# ArmMount_Board_2.net
KiCad netlist of a schematic drawn in EAGLE
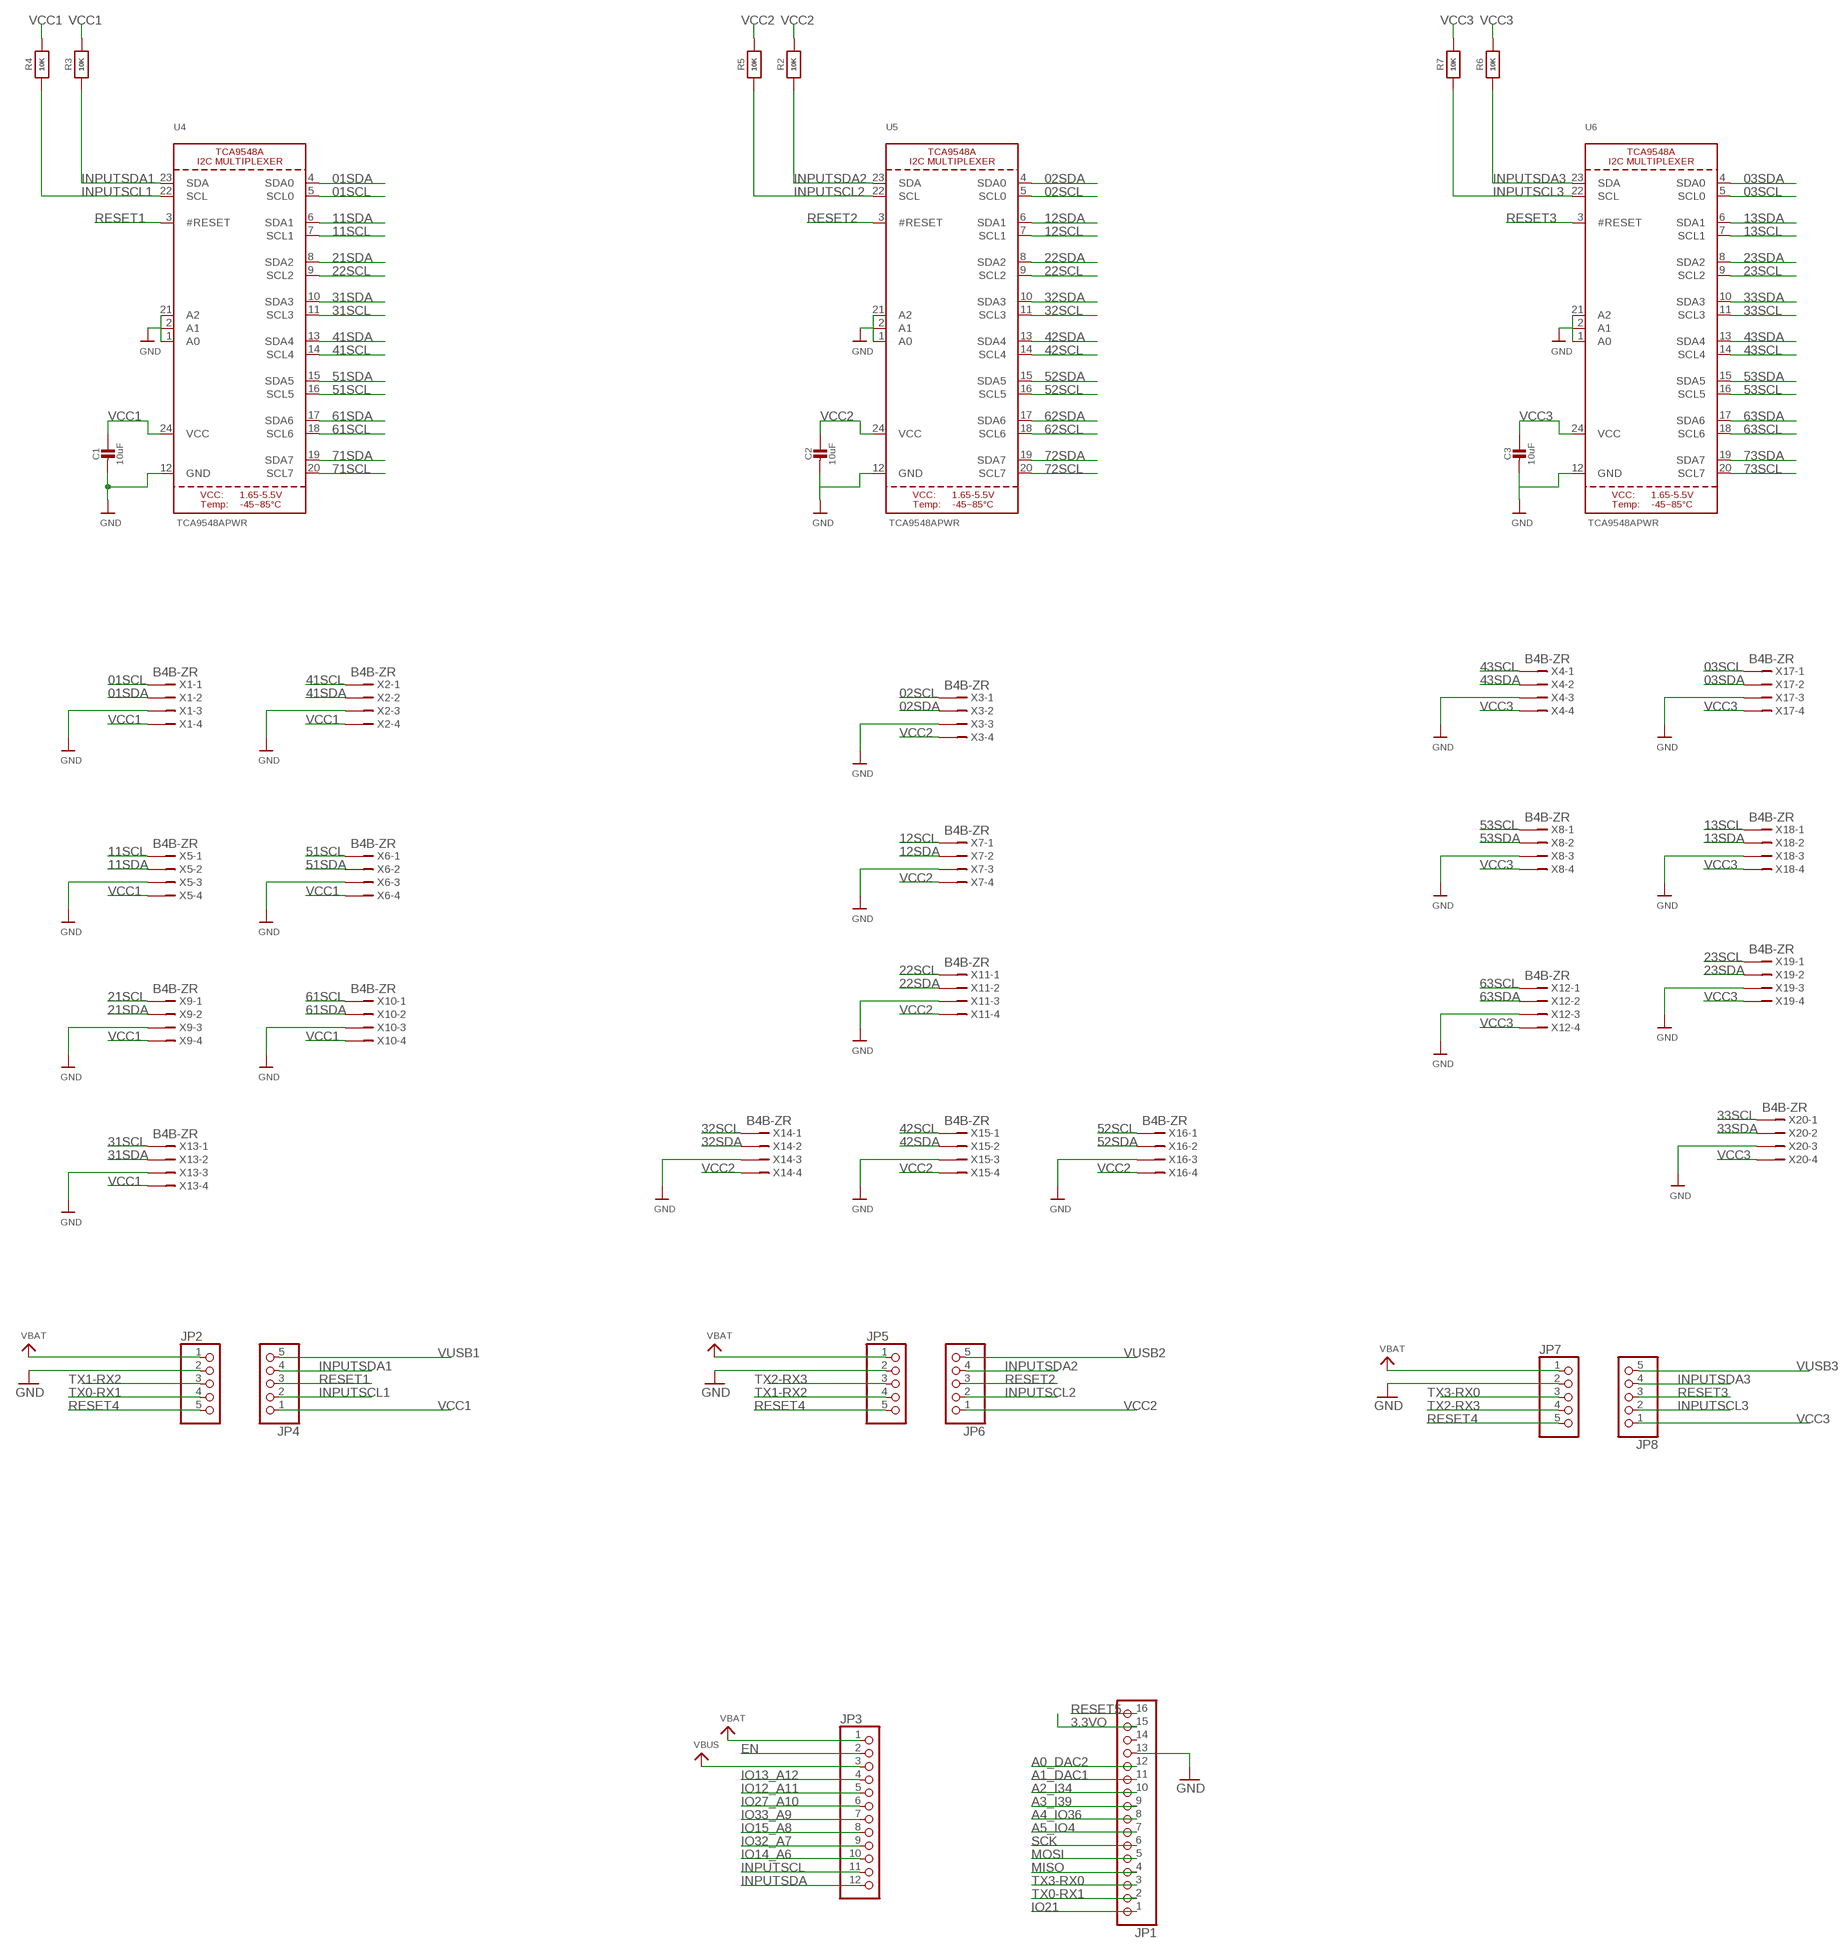
[diagram p0: schematic, sheet 1]

(export (version "E")
  (design (tool "Eeschema 10.0.6"))
  (components
    (comp (ref "C1")
      (value "10uF")
      (footprint "eagle-import:0805-NO")
      (libsource (lib "eagle-import") (part "CAP_CERAMIC0805-NOOUTLINE"))
    )
    (comp (ref "C2")
      (value "10uF")
      (footprint "eagle-import:0805-NO")
      (libsource (lib "eagle-import") (part "CAP_CERAMIC0805-NOOUTLINE"))
    )
    (comp (ref "C3")
      (value "10uF")
      (footprint "eagle-import:0805-NO")
      (libsource (lib "eagle-import") (part "CAP_CERAMIC0805-NOOUTLINE"))
    )
    (comp (ref "JP1")
      (value "HEADER-1X16_MIN")
      (footprint "eagle-import:1X16_ROUND_MIN")
      (libsource (lib "eagle-import") (part "HEADER-1X16_MIN"))
    )
    (comp (ref "JP2")
      (value "HEADER-1X576MIL")
      (footprint "eagle-import:1X05_ROUND_76")
      (libsource (lib "eagle-import") (part "HEADER-1X576MIL"))
    )
    (comp (ref "JP3")
      (value "HEADER-1X12_MIN")
      (footprint "eagle-import:1X12_ROUND_MIN")
      (libsource (lib "eagle-import") (part "HEADER-1X12_MIN"))
    )
    (comp (ref "JP4")
      (value "HEADER-1X576MIL")
      (footprint "eagle-import:1X05_ROUND_76")
      (libsource (lib "eagle-import") (part "HEADER-1X576MIL"))
    )
    (comp (ref "JP5")
      (value "HEADER-1X576MIL")
      (footprint "eagle-import:1X05_ROUND_76")
      (libsource (lib "eagle-import") (part "HEADER-1X576MIL"))
    )
    (comp (ref "JP6")
      (value "HEADER-1X576MIL")
      (footprint "eagle-import:1X05_ROUND_76")
      (libsource (lib "eagle-import") (part "HEADER-1X576MIL"))
    )
    (comp (ref "JP7")
      (value "HEADER-1X576MIL")
      (footprint "eagle-import:1X05_ROUND_76")
      (libsource (lib "eagle-import") (part "HEADER-1X576MIL"))
    )
    (comp (ref "JP8")
      (value "HEADER-1X576MIL")
      (footprint "eagle-import:1X05_ROUND_76")
      (libsource (lib "eagle-import") (part "HEADER-1X576MIL"))
    )
    (comp (ref "R2")
      (value "10K")
      (footprint "eagle-import:0805-NO")
      (libsource (lib "eagle-import") (part "RESISTOR0805_NOOUTLINE"))
    )
    (comp (ref "R3")
      (value "10K")
      (footprint "eagle-import:0805-NO")
      (libsource (lib "eagle-import") (part "RESISTOR0805_NOOUTLINE"))
    )
    (comp (ref "R4")
      (value "10K")
      (footprint "eagle-import:0805-NO")
      (libsource (lib "eagle-import") (part "RESISTOR0805_NOOUTLINE"))
    )
    (comp (ref "R5")
      (value "10K")
      (footprint "eagle-import:0805-NO")
      (libsource (lib "eagle-import") (part "RESISTOR0805_NOOUTLINE"))
    )
    (comp (ref "R6")
      (value "10K")
      (footprint "eagle-import:0805-NO")
      (libsource (lib "eagle-import") (part "RESISTOR0805_NOOUTLINE"))
    )
    (comp (ref "R7")
      (value "10K")
      (footprint "eagle-import:0805-NO")
      (libsource (lib "eagle-import") (part "RESISTOR0805_NOOUTLINE"))
    )
    (comp (ref "U4")
      (value "TCA9548APWR")
      (footprint "eagle-import:TSSOP24")
      (libsource (lib "eagle-import") (part "TCA9548A"))
    )
    (comp (ref "U5")
      (value "TCA9548APWR")
      (footprint "eagle-import:TSSOP24")
      (libsource (lib "eagle-import") (part "TCA9548A"))
    )
    (comp (ref "U6")
      (value "TCA9548APWR")
      (footprint "eagle-import:TSSOP24")
      (libsource (lib "eagle-import") (part "TCA9548A"))
    )
    (comp (ref "X1")
      (value "B4B-ZR")
      (footprint "eagle-import:B4B-ZR")
      (fields (field (name "MF") "FARNELL") (field (name "MPN") "B4B-ZR(LF)(SN)"))
      (libsource (lib "eagle-import") (part "?4B-ZRB"))
    )
    (comp (ref "X2")
      (value "B4B-ZR")
      (footprint "eagle-import:B4B-ZR")
      (fields (field (name "MF") "FARNELL") (field (name "MPN") "B4B-ZR(LF)(SN)"))
      (libsource (lib "eagle-import") (part "?4B-ZRB"))
    )
    (comp (ref "X3")
      (value "B4B-ZR")
      (footprint "eagle-import:B4B-ZR")
      (fields (field (name "MF") "FARNELL") (field (name "MPN") "B4B-ZR(LF)(SN)"))
      (libsource (lib "eagle-import") (part "?4B-ZRB"))
    )
    (comp (ref "X4")
      (value "B4B-ZR")
      (footprint "eagle-import:B4B-ZR")
      (fields (field (name "MF") "FARNELL") (field (name "MPN") "B4B-ZR(LF)(SN)"))
      (libsource (lib "eagle-import") (part "?4B-ZRB"))
    )
    (comp (ref "X5")
      (value "B4B-ZR")
      (footprint "eagle-import:B4B-ZR")
      (fields (field (name "MF") "FARNELL") (field (name "MPN") "B4B-ZR(LF)(SN)"))
      (libsource (lib "eagle-import") (part "?4B-ZRB"))
    )
    (comp (ref "X6")
      (value "B4B-ZR")
      (footprint "eagle-import:B4B-ZR")
      (fields (field (name "MF") "FARNELL") (field (name "MPN") "B4B-ZR(LF)(SN)"))
      (libsource (lib "eagle-import") (part "?4B-ZRB"))
    )
    (comp (ref "X7")
      (value "B4B-ZR")
      (footprint "eagle-import:B4B-ZR")
      (fields (field (name "MF") "FARNELL") (field (name "MPN") "B4B-ZR(LF)(SN)"))
      (libsource (lib "eagle-import") (part "?4B-ZRB"))
    )
    (comp (ref "X8")
      (value "B4B-ZR")
      (footprint "eagle-import:B4B-ZR")
      (fields (field (name "MF") "FARNELL") (field (name "MPN") "B4B-ZR(LF)(SN)"))
      (libsource (lib "eagle-import") (part "?4B-ZRB"))
    )
    (comp (ref "X9")
      (value "B4B-ZR")
      (footprint "eagle-import:B4B-ZR")
      (fields (field (name "MF") "FARNELL") (field (name "MPN") "B4B-ZR(LF)(SN)"))
      (libsource (lib "eagle-import") (part "?4B-ZRB"))
    )
    (comp (ref "X10")
      (value "B4B-ZR")
      (footprint "eagle-import:B4B-ZR")
      (fields (field (name "MF") "FARNELL") (field (name "MPN") "B4B-ZR(LF)(SN)"))
      (libsource (lib "eagle-import") (part "?4B-ZRB"))
    )
    (comp (ref "X11")
      (value "B4B-ZR")
      (footprint "eagle-import:B4B-ZR")
      (fields (field (name "MF") "FARNELL") (field (name "MPN") "B4B-ZR(LF)(SN)"))
      (libsource (lib "eagle-import") (part "?4B-ZRB"))
    )
    (comp (ref "X12")
      (value "B4B-ZR")
      (footprint "eagle-import:B4B-ZR")
      (fields (field (name "MF") "FARNELL") (field (name "MPN") "B4B-ZR(LF)(SN)"))
      (libsource (lib "eagle-import") (part "?4B-ZRB"))
    )
    (comp (ref "X13")
      (value "B4B-ZR")
      (footprint "eagle-import:B4B-ZR")
      (fields (field (name "MF") "FARNELL") (field (name "MPN") "B4B-ZR(LF)(SN)"))
      (libsource (lib "eagle-import") (part "?4B-ZRB"))
    )
    (comp (ref "X14")
      (value "B4B-ZR")
      (footprint "eagle-import:B4B-ZR")
      (fields (field (name "MF") "FARNELL") (field (name "MPN") "B4B-ZR(LF)(SN)"))
      (libsource (lib "eagle-import") (part "?4B-ZRB"))
    )
    (comp (ref "X15")
      (value "B4B-ZR")
      (footprint "eagle-import:B4B-ZR")
      (fields (field (name "MF") "FARNELL") (field (name "MPN") "B4B-ZR(LF)(SN)"))
      (libsource (lib "eagle-import") (part "?4B-ZRB"))
    )
    (comp (ref "X16")
      (value "B4B-ZR")
      (footprint "eagle-import:B4B-ZR")
      (fields (field (name "MF") "FARNELL") (field (name "MPN") "B4B-ZR(LF)(SN)"))
      (libsource (lib "eagle-import") (part "?4B-ZRB"))
    )
    (comp (ref "X17")
      (value "B4B-ZR")
      (footprint "eagle-import:B4B-ZR")
      (fields (field (name "MF") "FARNELL") (field (name "MPN") "B4B-ZR(LF)(SN)"))
      (libsource (lib "eagle-import") (part "?4B-ZRB"))
    )
    (comp (ref "X18")
      (value "B4B-ZR")
      (footprint "eagle-import:B4B-ZR")
      (fields (field (name "MF") "FARNELL") (field (name "MPN") "B4B-ZR(LF)(SN)"))
      (libsource (lib "eagle-import") (part "?4B-ZRB"))
    )
    (comp (ref "X19")
      (value "B4B-ZR")
      (footprint "eagle-import:B4B-ZR")
      (fields (field (name "MF") "FARNELL") (field (name "MPN") "B4B-ZR(LF)(SN)"))
      (libsource (lib "eagle-import") (part "?4B-ZRB"))
    )
    (comp (ref "X20")
      (value "B4B-ZR")
      (footprint "eagle-import:B4B-ZR")
      (fields (field (name "MF") "FARNELL") (field (name "MPN") "B4B-ZR(LF)(SN)"))
      (libsource (lib "eagle-import") (part "?4B-ZRB"))
    )
  )
  (nets
    (net (code "1") (name "/01SCL") (class "Default")
      (node (ref "U4") (pin "5") (pinfunction "SCL0_5") (pintype "bidirectional"))
      (node (ref "X1") (pin "1") (pinfunction "1_1") (pintype "passive"))
    )
    (net (code "2") (name "/01SDA") (class "Default")
      (node (ref "U4") (pin "4") (pinfunction "SDA0_4") (pintype "bidirectional"))
      (node (ref "X1") (pin "2") (pinfunction "1_2") (pintype "passive"))
    )
    (net (code "3") (name "/02SCL") (class "Default")
      (node (ref "U5") (pin "5") (pinfunction "SCL0_5") (pintype "bidirectional"))
      (node (ref "X3") (pin "1") (pinfunction "1_1") (pintype "passive"))
    )
    (net (code "4") (name "/02SDA") (class "Default")
      (node (ref "U5") (pin "4") (pinfunction "SDA0_4") (pintype "bidirectional"))
      (node (ref "X3") (pin "2") (pinfunction "1_2") (pintype "passive"))
    )
    (net (code "5") (name "/3.3VO") (class "Default")
      (node (ref "JP1") (pin "15") (pinfunction "15_15") (pintype "passive"))
    )
    (net (code "6") (name "/03SCL") (class "Default")
      (node (ref "U6") (pin "5") (pinfunction "SCL0_5") (pintype "bidirectional"))
      (node (ref "X17") (pin "1") (pinfunction "1_1") (pintype "passive"))
    )
    (net (code "7") (name "/03SDA") (class "Default")
      (node (ref "U6") (pin "4") (pinfunction "SDA0_4") (pintype "bidirectional"))
      (node (ref "X17") (pin "2") (pinfunction "1_2") (pintype "passive"))
    )
    (net (code "8") (name "/11SCL") (class "Default")
      (node (ref "U4") (pin "7") (pinfunction "SCL1_7") (pintype "bidirectional"))
      (node (ref "X5") (pin "1") (pinfunction "1_1") (pintype "passive"))
    )
    (net (code "9") (name "/11SDA") (class "Default")
      (node (ref "U4") (pin "6") (pinfunction "SDA1_6") (pintype "bidirectional"))
      (node (ref "X5") (pin "2") (pinfunction "1_2") (pintype "passive"))
    )
    (net (code "10") (name "/12SCL") (class "Default")
      (node (ref "U5") (pin "7") (pinfunction "SCL1_7") (pintype "bidirectional"))
      (node (ref "X7") (pin "1") (pinfunction "1_1") (pintype "passive"))
    )
    (net (code "11") (name "/12SDA") (class "Default")
      (node (ref "U5") (pin "6") (pinfunction "SDA1_6") (pintype "bidirectional"))
      (node (ref "X7") (pin "2") (pinfunction "1_2") (pintype "passive"))
    )
    (net (code "12") (name "/13SCL") (class "Default")
      (node (ref "U6") (pin "7") (pinfunction "SCL1_7") (pintype "bidirectional"))
      (node (ref "X18") (pin "1") (pinfunction "1_1") (pintype "passive"))
    )
    (net (code "13") (name "/13SDA") (class "Default")
      (node (ref "U6") (pin "6") (pinfunction "SDA1_6") (pintype "bidirectional"))
      (node (ref "X18") (pin "2") (pinfunction "1_2") (pintype "passive"))
    )
    (net (code "14") (name "/21SCL") (class "Default")
      (node (ref "X9") (pin "1") (pinfunction "1_1") (pintype "passive"))
    )
    (net (code "15") (name "/21SDA") (class "Default")
      (node (ref "U4") (pin "8") (pinfunction "SDA2_8") (pintype "bidirectional"))
      (node (ref "X9") (pin "2") (pinfunction "1_2") (pintype "passive"))
    )
    (net (code "16") (name "/22SCL") (class "Default")
      (node (ref "U4") (pin "9") (pinfunction "SCL2_9") (pintype "bidirectional"))
      (node (ref "U5") (pin "9") (pinfunction "SCL2_9") (pintype "bidirectional"))
      (node (ref "X11") (pin "1") (pinfunction "1_1") (pintype "passive"))
    )
    (net (code "17") (name "/22SDA") (class "Default")
      (node (ref "U5") (pin "8") (pinfunction "SDA2_8") (pintype "bidirectional"))
      (node (ref "X11") (pin "2") (pinfunction "1_2") (pintype "passive"))
    )
    (net (code "18") (name "/23SCL") (class "Default")
      (node (ref "U6") (pin "9") (pinfunction "SCL2_9") (pintype "bidirectional"))
      (node (ref "X19") (pin "1") (pinfunction "1_1") (pintype "passive"))
    )
    (net (code "19") (name "/23SDA") (class "Default")
      (node (ref "U6") (pin "8") (pinfunction "SDA2_8") (pintype "bidirectional"))
      (node (ref "X19") (pin "2") (pinfunction "1_2") (pintype "passive"))
    )
    (net (code "20") (name "/31SCL") (class "Default")
      (node (ref "U4") (pin "11") (pinfunction "SCL3_11") (pintype "bidirectional"))
      (node (ref "X13") (pin "1") (pinfunction "1_1") (pintype "passive"))
    )
    (net (code "21") (name "/31SDA") (class "Default")
      (node (ref "U4") (pin "10") (pinfunction "SDA3_10") (pintype "bidirectional"))
      (node (ref "X13") (pin "2") (pinfunction "1_2") (pintype "passive"))
    )
    (net (code "22") (name "/32SCL") (class "Default")
      (node (ref "U5") (pin "11") (pinfunction "SCL3_11") (pintype "bidirectional"))
      (node (ref "X14") (pin "1") (pinfunction "1_1") (pintype "passive"))
    )
    (net (code "23") (name "/32SDA") (class "Default")
      (node (ref "U5") (pin "10") (pinfunction "SDA3_10") (pintype "bidirectional"))
      (node (ref "X14") (pin "2") (pinfunction "1_2") (pintype "passive"))
    )
    (net (code "24") (name "/33SCL") (class "Default")
      (node (ref "U6") (pin "11") (pinfunction "SCL3_11") (pintype "bidirectional"))
      (node (ref "X20") (pin "1") (pinfunction "1_1") (pintype "passive"))
    )
    (net (code "25") (name "/33SDA") (class "Default")
      (node (ref "U6") (pin "10") (pinfunction "SDA3_10") (pintype "bidirectional"))
      (node (ref "X20") (pin "2") (pinfunction "1_2") (pintype "passive"))
    )
    (net (code "26") (name "/41SCL") (class "Default")
      (node (ref "U4") (pin "14") (pinfunction "SCL4_14") (pintype "bidirectional"))
      (node (ref "X2") (pin "1") (pinfunction "1_1") (pintype "passive"))
    )
    (net (code "27") (name "/41SDA") (class "Default")
      (node (ref "U4") (pin "13") (pinfunction "SDA4_13") (pintype "bidirectional"))
      (node (ref "X2") (pin "2") (pinfunction "1_2") (pintype "passive"))
    )
    (net (code "28") (name "/42SCL") (class "Default")
      (node (ref "U5") (pin "14") (pinfunction "SCL4_14") (pintype "bidirectional"))
      (node (ref "X15") (pin "1") (pinfunction "1_1") (pintype "passive"))
    )
    (net (code "29") (name "/42SDA") (class "Default")
      (node (ref "U5") (pin "13") (pinfunction "SDA4_13") (pintype "bidirectional"))
      (node (ref "X15") (pin "2") (pinfunction "1_2") (pintype "passive"))
    )
    (net (code "30") (name "/43SCL") (class "Default")
      (node (ref "U6") (pin "14") (pinfunction "SCL4_14") (pintype "bidirectional"))
      (node (ref "X4") (pin "1") (pinfunction "1_1") (pintype "passive"))
    )
    (net (code "31") (name "/43SDA") (class "Default")
      (node (ref "U6") (pin "13") (pinfunction "SDA4_13") (pintype "bidirectional"))
      (node (ref "X4") (pin "2") (pinfunction "1_2") (pintype "passive"))
    )
    (net (code "32") (name "/51SCL") (class "Default")
      (node (ref "U4") (pin "16") (pinfunction "SCL5_16") (pintype "bidirectional"))
      (node (ref "X6") (pin "1") (pinfunction "1_1") (pintype "passive"))
    )
    (net (code "33") (name "/51SDA") (class "Default")
      (node (ref "U4") (pin "15") (pinfunction "SDA5_15") (pintype "bidirectional"))
      (node (ref "X6") (pin "2") (pinfunction "1_2") (pintype "passive"))
    )
    (net (code "34") (name "/52SCL") (class "Default")
      (node (ref "U5") (pin "16") (pinfunction "SCL5_16") (pintype "bidirectional"))
      (node (ref "X16") (pin "1") (pinfunction "1_1") (pintype "passive"))
    )
    (net (code "35") (name "/52SDA") (class "Default")
      (node (ref "U5") (pin "15") (pinfunction "SDA5_15") (pintype "bidirectional"))
      (node (ref "X16") (pin "2") (pinfunction "1_2") (pintype "passive"))
    )
    (net (code "36") (name "/53SCL") (class "Default")
      (node (ref "U6") (pin "16") (pinfunction "SCL5_16") (pintype "bidirectional"))
      (node (ref "X8") (pin "1") (pinfunction "1_1") (pintype "passive"))
    )
    (net (code "37") (name "/53SDA") (class "Default")
      (node (ref "U6") (pin "15") (pinfunction "SDA5_15") (pintype "bidirectional"))
      (node (ref "X8") (pin "2") (pinfunction "1_2") (pintype "passive"))
    )
    (net (code "38") (name "/61SCL") (class "Default")
      (node (ref "U4") (pin "18") (pinfunction "SCL6_18") (pintype "bidirectional"))
      (node (ref "X10") (pin "1") (pinfunction "1_1") (pintype "passive"))
    )
    (net (code "39") (name "/61SDA") (class "Default")
      (node (ref "U4") (pin "17") (pinfunction "SDA6_17") (pintype "bidirectional"))
      (node (ref "X10") (pin "2") (pinfunction "1_2") (pintype "passive"))
    )
    (net (code "40") (name "/62SCL") (class "Default")
      (node (ref "U5") (pin "18") (pinfunction "SCL6_18") (pintype "bidirectional"))
    )
    (net (code "41") (name "/62SDA") (class "Default")
      (node (ref "U5") (pin "17") (pinfunction "SDA6_17") (pintype "bidirectional"))
    )
    (net (code "42") (name "/63SCL") (class "Default")
      (node (ref "U6") (pin "18") (pinfunction "SCL6_18") (pintype "bidirectional"))
      (node (ref "X12") (pin "1") (pinfunction "1_1") (pintype "passive"))
    )
    (net (code "43") (name "/63SDA") (class "Default")
      (node (ref "U6") (pin "17") (pinfunction "SDA6_17") (pintype "bidirectional"))
      (node (ref "X12") (pin "2") (pinfunction "1_2") (pintype "passive"))
    )
    (net (code "44") (name "/71SCL") (class "Default")
      (node (ref "U4") (pin "20") (pinfunction "SCL7_20") (pintype "bidirectional"))
    )
    (net (code "45") (name "/71SDA") (class "Default")
      (node (ref "U4") (pin "19") (pinfunction "SDA7_19") (pintype "bidirectional"))
    )
    (net (code "46") (name "/72SCL") (class "Default")
      (node (ref "U5") (pin "20") (pinfunction "SCL7_20") (pintype "bidirectional"))
    )
    (net (code "47") (name "/72SDA") (class "Default")
      (node (ref "U5") (pin "19") (pinfunction "SDA7_19") (pintype "bidirectional"))
    )
    (net (code "48") (name "/73SCL") (class "Default")
      (node (ref "U6") (pin "20") (pinfunction "SCL7_20") (pintype "bidirectional"))
    )
    (net (code "49") (name "/73SDA") (class "Default")
      (node (ref "U6") (pin "19") (pinfunction "SDA7_19") (pintype "bidirectional"))
    )
    (net (code "50") (name "/A0_DAC2") (class "Default")
      (node (ref "JP1") (pin "12") (pinfunction "12_12") (pintype "passive"))
    )
    (net (code "51") (name "/A1_DAC1") (class "Default")
      (node (ref "JP1") (pin "11") (pinfunction "11_11") (pintype "passive"))
    )
    (net (code "52") (name "/A2_I34") (class "Default")
      (node (ref "JP1") (pin "10") (pinfunction "10_10") (pintype "passive"))
    )
    (net (code "53") (name "/A3_I39") (class "Default")
      (node (ref "JP1") (pin "9") (pinfunction "9_9") (pintype "passive"))
    )
    (net (code "54") (name "/A4_IO36") (class "Default")
      (node (ref "JP1") (pin "8") (pinfunction "8_8") (pintype "passive"))
    )
    (net (code "55") (name "/A5_IO4") (class "Default")
      (node (ref "JP1") (pin "7") (pinfunction "7_7") (pintype "passive"))
    )
    (net (code "56") (name "/EN") (class "Default")
      (node (ref "JP3") (pin "2") (pinfunction "2_2") (pintype "passive"))
    )
    (net (code "57") (name "/INPUTSCL") (class "Default")
      (node (ref "JP3") (pin "11") (pinfunction "11_11") (pintype "passive"))
    )
    (net (code "58") (name "/INPUTSCL1") (class "Default")
      (node (ref "JP4") (pin "2") (pinfunction "2_2") (pintype "passive"))
      (node (ref "R4") (pin "1") (pinfunction "1_1") (pintype "passive"))
      (node (ref "U4") (pin "22") (pinfunction "SCL_22") (pintype "bidirectional"))
    )
    (net (code "59") (name "/INPUTSCL2") (class "Default")
      (node (ref "JP6") (pin "2") (pinfunction "2_2") (pintype "passive"))
      (node (ref "R5") (pin "1") (pinfunction "1_1") (pintype "passive"))
      (node (ref "U5") (pin "22") (pinfunction "SCL_22") (pintype "bidirectional"))
    )
    (net (code "60") (name "/INPUTSCL3") (class "Default")
      (node (ref "JP8") (pin "2") (pinfunction "2_2") (pintype "passive"))
      (node (ref "R7") (pin "1") (pinfunction "1_1") (pintype "passive"))
      (node (ref "U6") (pin "22") (pinfunction "SCL_22") (pintype "bidirectional"))
    )
    (net (code "61") (name "/INPUTSDA") (class "Default")
      (node (ref "JP3") (pin "12") (pinfunction "12_12") (pintype "passive"))
    )
    (net (code "62") (name "/INPUTSDA1") (class "Default")
      (node (ref "JP4") (pin "4") (pinfunction "4_4") (pintype "passive"))
      (node (ref "R3") (pin "1") (pinfunction "1_1") (pintype "passive"))
      (node (ref "U4") (pin "23") (pinfunction "SDA_23") (pintype "bidirectional"))
    )
    (net (code "63") (name "/INPUTSDA2") (class "Default")
      (node (ref "JP6") (pin "4") (pinfunction "4_4") (pintype "passive"))
      (node (ref "R2") (pin "1") (pinfunction "1_1") (pintype "passive"))
      (node (ref "U5") (pin "23") (pinfunction "SDA_23") (pintype "bidirectional"))
    )
    (net (code "64") (name "/INPUTSDA3") (class "Default")
      (node (ref "JP8") (pin "4") (pinfunction "4_4") (pintype "passive"))
      (node (ref "R6") (pin "1") (pinfunction "1_1") (pintype "passive"))
      (node (ref "U6") (pin "23") (pinfunction "SDA_23") (pintype "bidirectional"))
    )
    (net (code "65") (name "/IO12_A11") (class "Default")
      (node (ref "JP3") (pin "5") (pinfunction "5_5") (pintype "passive"))
    )
    (net (code "66") (name "/IO13_A12") (class "Default")
      (node (ref "JP3") (pin "4") (pinfunction "4_4") (pintype "passive"))
    )
    (net (code "67") (name "/IO14_A6") (class "Default")
      (node (ref "JP3") (pin "10") (pinfunction "10_10") (pintype "passive"))
    )
    (net (code "68") (name "/IO15_A8") (class "Default")
      (node (ref "JP3") (pin "8") (pinfunction "8_8") (pintype "passive"))
    )
    (net (code "69") (name "/IO21") (class "Default")
      (node (ref "JP1") (pin "1") (pinfunction "1_1") (pintype "passive"))
    )
    (net (code "70") (name "/IO27_A10") (class "Default")
      (node (ref "JP3") (pin "6") (pinfunction "6_6") (pintype "passive"))
    )
    (net (code "71") (name "/IO32_A7") (class "Default")
      (node (ref "JP3") (pin "9") (pinfunction "9_9") (pintype "passive"))
    )
    (net (code "72") (name "/IO33_A9") (class "Default")
      (node (ref "JP3") (pin "7") (pinfunction "7_7") (pintype "passive"))
    )
    (net (code "73") (name "/MISO") (class "Default")
      (node (ref "JP1") (pin "4") (pinfunction "4_4") (pintype "passive"))
    )
    (net (code "74") (name "/MOSI") (class "Default")
      (node (ref "JP1") (pin "5") (pinfunction "5_5") (pintype "passive"))
    )
    (net (code "75") (name "/RESET1") (class "Default")
      (node (ref "JP4") (pin "3") (pinfunction "3_3") (pintype "passive"))
      (node (ref "U4") (pin "3") (pinfunction "#RESET_3") (pintype "bidirectional"))
    )
    (net (code "76") (name "/RESET2") (class "Default")
      (node (ref "JP6") (pin "3") (pinfunction "3_3") (pintype "passive"))
      (node (ref "U5") (pin "3") (pinfunction "#RESET_3") (pintype "bidirectional"))
    )
    (net (code "77") (name "/RESET3") (class "Default")
      (node (ref "JP8") (pin "3") (pinfunction "3_3") (pintype "passive"))
      (node (ref "U6") (pin "3") (pinfunction "#RESET_3") (pintype "bidirectional"))
    )
    (net (code "78") (name "/RESET4") (class "Default")
      (node (ref "JP2") (pin "5") (pinfunction "5_5") (pintype "passive"))
      (node (ref "JP5") (pin "5") (pinfunction "5_5") (pintype "passive"))
      (node (ref "JP7") (pin "5") (pinfunction "5_5") (pintype "passive"))
    )
    (net (code "79") (name "/RESET5") (class "Default")
      (node (ref "JP1") (pin "16") (pinfunction "16_16") (pintype "passive"))
    )
    (net (code "80") (name "/SCK") (class "Default")
      (node (ref "JP1") (pin "6") (pinfunction "6_6") (pintype "passive"))
    )
    (net (code "81") (name "/TX0-RX1") (class "Default")
      (node (ref "JP1") (pin "2") (pinfunction "2_2") (pintype "passive"))
      (node (ref "JP2") (pin "4") (pinfunction "4_4") (pintype "passive"))
    )
    (net (code "82") (name "/TX1-RX2") (class "Default")
      (node (ref "JP2") (pin "3") (pinfunction "3_3") (pintype "passive"))
      (node (ref "JP5") (pin "4") (pinfunction "4_4") (pintype "passive"))
    )
    (net (code "83") (name "/TX2-RX3") (class "Default")
      (node (ref "JP5") (pin "3") (pinfunction "3_3") (pintype "passive"))
      (node (ref "JP7") (pin "4") (pinfunction "4_4") (pintype "passive"))
    )
    (net (code "84") (name "/TX3-RX0") (class "Default")
      (node (ref "JP1") (pin "3") (pinfunction "3_3") (pintype "passive"))
      (node (ref "JP7") (pin "3") (pinfunction "3_3") (pintype "passive"))
    )
    (net (code "85") (name "/VCC1") (class "Default")
      (node (ref "C1") (pin "1") (pinfunction "1_1") (pintype "passive"))
      (node (ref "JP4") (pin "1") (pinfunction "1_1") (pintype "passive"))
      (node (ref "R3") (pin "2") (pinfunction "2_2") (pintype "passive"))
      (node (ref "R4") (pin "2") (pinfunction "2_2") (pintype "passive"))
      (node (ref "U4") (pin "24") (pinfunction "VCC_24") (pintype "bidirectional"))
      (node (ref "X1") (pin "4") (pinfunction "1_4") (pintype "passive"))
      (node (ref "X10") (pin "4") (pinfunction "1_4") (pintype "passive"))
      (node (ref "X13") (pin "4") (pinfunction "1_4") (pintype "passive"))
      (node (ref "X2") (pin "4") (pinfunction "1_4") (pintype "passive"))
      (node (ref "X5") (pin "4") (pinfunction "1_4") (pintype "passive"))
      (node (ref "X6") (pin "4") (pinfunction "1_4") (pintype "passive"))
      (node (ref "X9") (pin "4") (pinfunction "1_4") (pintype "passive"))
    )
    (net (code "86") (name "/VCC2") (class "Default")
      (node (ref "C2") (pin "1") (pinfunction "1_1") (pintype "passive"))
      (node (ref "JP6") (pin "1") (pinfunction "1_1") (pintype "passive"))
      (node (ref "R2") (pin "2") (pinfunction "2_2") (pintype "passive"))
      (node (ref "R5") (pin "2") (pinfunction "2_2") (pintype "passive"))
      (node (ref "U5") (pin "24") (pinfunction "VCC_24") (pintype "bidirectional"))
      (node (ref "X11") (pin "4") (pinfunction "1_4") (pintype "passive"))
      (node (ref "X14") (pin "4") (pinfunction "1_4") (pintype "passive"))
      (node (ref "X15") (pin "4") (pinfunction "1_4") (pintype "passive"))
      (node (ref "X16") (pin "4") (pinfunction "1_4") (pintype "passive"))
      (node (ref "X3") (pin "4") (pinfunction "1_4") (pintype "passive"))
      (node (ref "X7") (pin "4") (pinfunction "1_4") (pintype "passive"))
    )
    (net (code "87") (name "/VCC3") (class "Default")
      (node (ref "C3") (pin "1") (pinfunction "1_1") (pintype "passive"))
      (node (ref "JP8") (pin "1") (pinfunction "1_1") (pintype "passive"))
      (node (ref "R6") (pin "2") (pinfunction "2_2") (pintype "passive"))
      (node (ref "R7") (pin "2") (pinfunction "2_2") (pintype "passive"))
      (node (ref "U6") (pin "24") (pinfunction "VCC_24") (pintype "bidirectional"))
      (node (ref "X12") (pin "4") (pinfunction "1_4") (pintype "passive"))
      (node (ref "X17") (pin "4") (pinfunction "1_4") (pintype "passive"))
      (node (ref "X18") (pin "4") (pinfunction "1_4") (pintype "passive"))
      (node (ref "X19") (pin "4") (pinfunction "1_4") (pintype "passive"))
      (node (ref "X20") (pin "4") (pinfunction "1_4") (pintype "passive"))
      (node (ref "X4") (pin "4") (pinfunction "1_4") (pintype "passive"))
      (node (ref "X8") (pin "4") (pinfunction "1_4") (pintype "passive"))
    )
    (net (code "88") (name "/VUSB1") (class "Default")
      (node (ref "JP4") (pin "5") (pinfunction "5_5") (pintype "passive"))
    )
    (net (code "89") (name "/VUSB2") (class "Default")
      (node (ref "JP6") (pin "5") (pinfunction "5_5") (pintype "passive"))
    )
    (net (code "90") (name "/VUSB3") (class "Default")
      (node (ref "JP8") (pin "5") (pinfunction "5_5") (pintype "passive"))
    )
    (net (code "91") (name "GND") (class "Default")
      (node (ref "C1") (pin "2") (pinfunction "2_2") (pintype "passive"))
      (node (ref "C2") (pin "2") (pinfunction "2_2") (pintype "passive"))
      (node (ref "C3") (pin "2") (pinfunction "2_2") (pintype "passive"))
      (node (ref "JP1") (pin "13") (pinfunction "13_13") (pintype "passive"))
      (node (ref "JP2") (pin "2") (pinfunction "2_2") (pintype "passive"))
      (node (ref "JP5") (pin "2") (pinfunction "2_2") (pintype "passive"))
      (node (ref "JP7") (pin "2") (pinfunction "2_2") (pintype "passive"))
      (node (ref "U4") (pin "1") (pinfunction "A0_1") (pintype "bidirectional"))
      (node (ref "U4") (pin "12") (pinfunction "GND_12") (pintype "bidirectional"))
      (node (ref "U4") (pin "2") (pinfunction "A1_2") (pintype "bidirectional"))
      (node (ref "U4") (pin "21") (pinfunction "A2_21") (pintype "bidirectional"))
      (node (ref "U5") (pin "1") (pinfunction "A0_1") (pintype "bidirectional"))
      (node (ref "U5") (pin "12") (pinfunction "GND_12") (pintype "bidirectional"))
      (node (ref "U5") (pin "2") (pinfunction "A1_2") (pintype "bidirectional"))
      (node (ref "U5") (pin "21") (pinfunction "A2_21") (pintype "bidirectional"))
      (node (ref "U6") (pin "1") (pinfunction "A0_1") (pintype "bidirectional"))
      (node (ref "U6") (pin "12") (pinfunction "GND_12") (pintype "bidirectional"))
      (node (ref "U6") (pin "2") (pinfunction "A1_2") (pintype "bidirectional"))
      (node (ref "U6") (pin "21") (pinfunction "A2_21") (pintype "bidirectional"))
      (node (ref "X1") (pin "3") (pinfunction "1_3") (pintype "passive"))
      (node (ref "X10") (pin "3") (pinfunction "1_3") (pintype "passive"))
      (node (ref "X11") (pin "3") (pinfunction "1_3") (pintype "passive"))
      (node (ref "X12") (pin "3") (pinfunction "1_3") (pintype "passive"))
      (node (ref "X13") (pin "3") (pinfunction "1_3") (pintype "passive"))
      (node (ref "X14") (pin "3") (pinfunction "1_3") (pintype "passive"))
      (node (ref "X15") (pin "3") (pinfunction "1_3") (pintype "passive"))
      (node (ref "X16") (pin "3") (pinfunction "1_3") (pintype "passive"))
      (node (ref "X17") (pin "3") (pinfunction "1_3") (pintype "passive"))
      (node (ref "X18") (pin "3") (pinfunction "1_3") (pintype "passive"))
      (node (ref "X19") (pin "3") (pinfunction "1_3") (pintype "passive"))
      (node (ref "X2") (pin "3") (pinfunction "1_3") (pintype "passive"))
      (node (ref "X20") (pin "3") (pinfunction "1_3") (pintype "passive"))
      (node (ref "X3") (pin "3") (pinfunction "1_3") (pintype "passive"))
      (node (ref "X4") (pin "3") (pinfunction "1_3") (pintype "passive"))
      (node (ref "X5") (pin "3") (pinfunction "1_3") (pintype "passive"))
      (node (ref "X6") (pin "3") (pinfunction "1_3") (pintype "passive"))
      (node (ref "X7") (pin "3") (pinfunction "1_3") (pintype "passive"))
      (node (ref "X8") (pin "3") (pinfunction "1_3") (pintype "passive"))
      (node (ref "X9") (pin "3") (pinfunction "1_3") (pintype "passive"))
    )
    (net (code "92") (name "VBAT") (class "Default")
      (node (ref "JP2") (pin "1") (pinfunction "1_1") (pintype "passive"))
      (node (ref "JP3") (pin "1") (pinfunction "1_1") (pintype "passive"))
      (node (ref "JP5") (pin "1") (pinfunction "1_1") (pintype "passive"))
      (node (ref "JP7") (pin "1") (pinfunction "1_1") (pintype "passive"))
    )
    (net (code "93") (name "VBUS") (class "Default")
      (node (ref "JP3") (pin "3") (pinfunction "3_3") (pintype "passive"))
    )
    (net (code "94") (name "unconnected-(JP1-Pad14)") (class "Default")
      (node (ref "JP1") (pin "14") (pinfunction "14_14") (pintype "passive"))
    )
  )
)
